# untitled.net
KiCad netlist of a schematic drawn in EAGLE
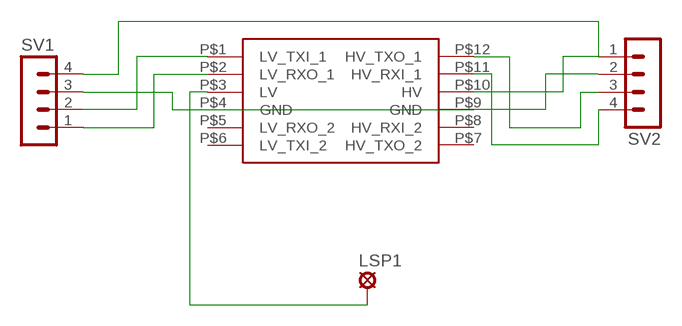
[diagram p0: schematic, sheet 1]

(export (version "E")
  (design (tool "Eeschema 10.0.6"))
  (components
    (comp (ref "LSP1")
      (value "MCS08")
      (footprint "eagle-import:MCS08")
      (libsource (lib "eagle-import") (part "MCS08"))
    )
    (comp (ref "SV1")
      (value "MA04-1")
      (footprint "eagle-import:MA04-1")
      (libsource (lib "eagle-import") (part "MA04-1"))
    )
    (comp (ref "SV2")
      (value "MA04-1")
      (footprint "eagle-import:MA04-1")
      (libsource (lib "eagle-import") (part "MA04-1"))
    )
    (comp (ref "U$1")
      (value "LOGIC_LEVEL_CONVERTER")
      (footprint "eagle-import:LOGIC_LEVEL_CONVERTER")
      (libsource (lib "eagle-import") (part "LOGIC_LEVEL_CONVERTER"))
    )
  )
  (nets
    (net (code "1") (name "Net-(SV1-Pad3)") (class "Default")
      (node (ref "SV1") (pin "3") (pinfunction "3_3") (pintype "passive"))
      (node (ref "SV2") (pin "2") (pinfunction "2_2") (pintype "passive"))
      (node (ref "U$1") (pin "P$4") (pinfunction "GND_P$4") (pintype "bidirectional"))
      (node (ref "U$1") (pin "P$9") (pinfunction "GND_P$9") (pintype "bidirectional"))
    )
    (net (code "2") (name "Net-(U$1-HV)") (class "Default")
      (node (ref "SV1") (pin "4") (pinfunction "4_4") (pintype "passive"))
      (node (ref "SV2") (pin "1") (pinfunction "1_1") (pintype "passive"))
      (node (ref "U$1") (pin "P$10") (pinfunction "HV_P$10") (pintype "bidirectional"))
    )
    (net (code "3") (name "Net-(U$1-HV_RXI_1)") (class "Default")
      (node (ref "SV2") (pin "4") (pinfunction "4_4") (pintype "passive"))
      (node (ref "U$1") (pin "P$11") (pinfunction "HV_RXI_1_P$11") (pintype "bidirectional"))
    )
    (net (code "4") (name "Net-(U$1-HV_TXO_1)") (class "Default")
      (node (ref "SV2") (pin "3") (pinfunction "3_3") (pintype "passive"))
      (node (ref "U$1") (pin "P$12") (pinfunction "HV_TXO_1_P$12") (pintype "bidirectional"))
    )
    (net (code "5") (name "Net-(U$1-LV)") (class "Default")
      (node (ref "LSP1") (pin "MP") (pinfunction "MP_MP") (pintype "passive"))
      (node (ref "U$1") (pin "P$3") (pinfunction "LV_P$3") (pintype "bidirectional"))
    )
    (net (code "6") (name "Net-(U$1-LV_RXO_1)") (class "Default")
      (node (ref "SV1") (pin "1") (pinfunction "1_1") (pintype "passive"))
      (node (ref "U$1") (pin "P$2") (pinfunction "LV_RXO_1_P$2") (pintype "bidirectional"))
    )
    (net (code "7") (name "Net-(U$1-LV_TXI_1)") (class "Default")
      (node (ref "SV1") (pin "2") (pinfunction "2_2") (pintype "passive"))
      (node (ref "U$1") (pin "P$1") (pinfunction "LV_TXI_1_P$1") (pintype "bidirectional"))
    )
    (net (code "8") (name "unconnected-(U$1-HV_RXI_2-PadP$8)") (class "Default")
      (node (ref "U$1") (pin "P$8") (pinfunction "HV_RXI_2_P$8") (pintype "bidirectional"))
    )
    (net (code "9") (name "unconnected-(U$1-HV_TXO_2-PadP$7)") (class "Default")
      (node (ref "U$1") (pin "P$7") (pinfunction "HV_TXO_2_P$7") (pintype "bidirectional"))
    )
    (net (code "10") (name "unconnected-(U$1-LV_RXO_2-PadP$5)") (class "Default")
      (node (ref "U$1") (pin "P$5") (pinfunction "LV_RXO_2_P$5") (pintype "bidirectional"))
    )
    (net (code "11") (name "unconnected-(U$1-LV_TXI_2-PadP$6)") (class "Default")
      (node (ref "U$1") (pin "P$6") (pinfunction "LV_TXI_2_P$6") (pintype "bidirectional"))
    )
  )
)
